# RGB2HDMI.net
KiCad netlist of a schematic drawn in Altium Designer
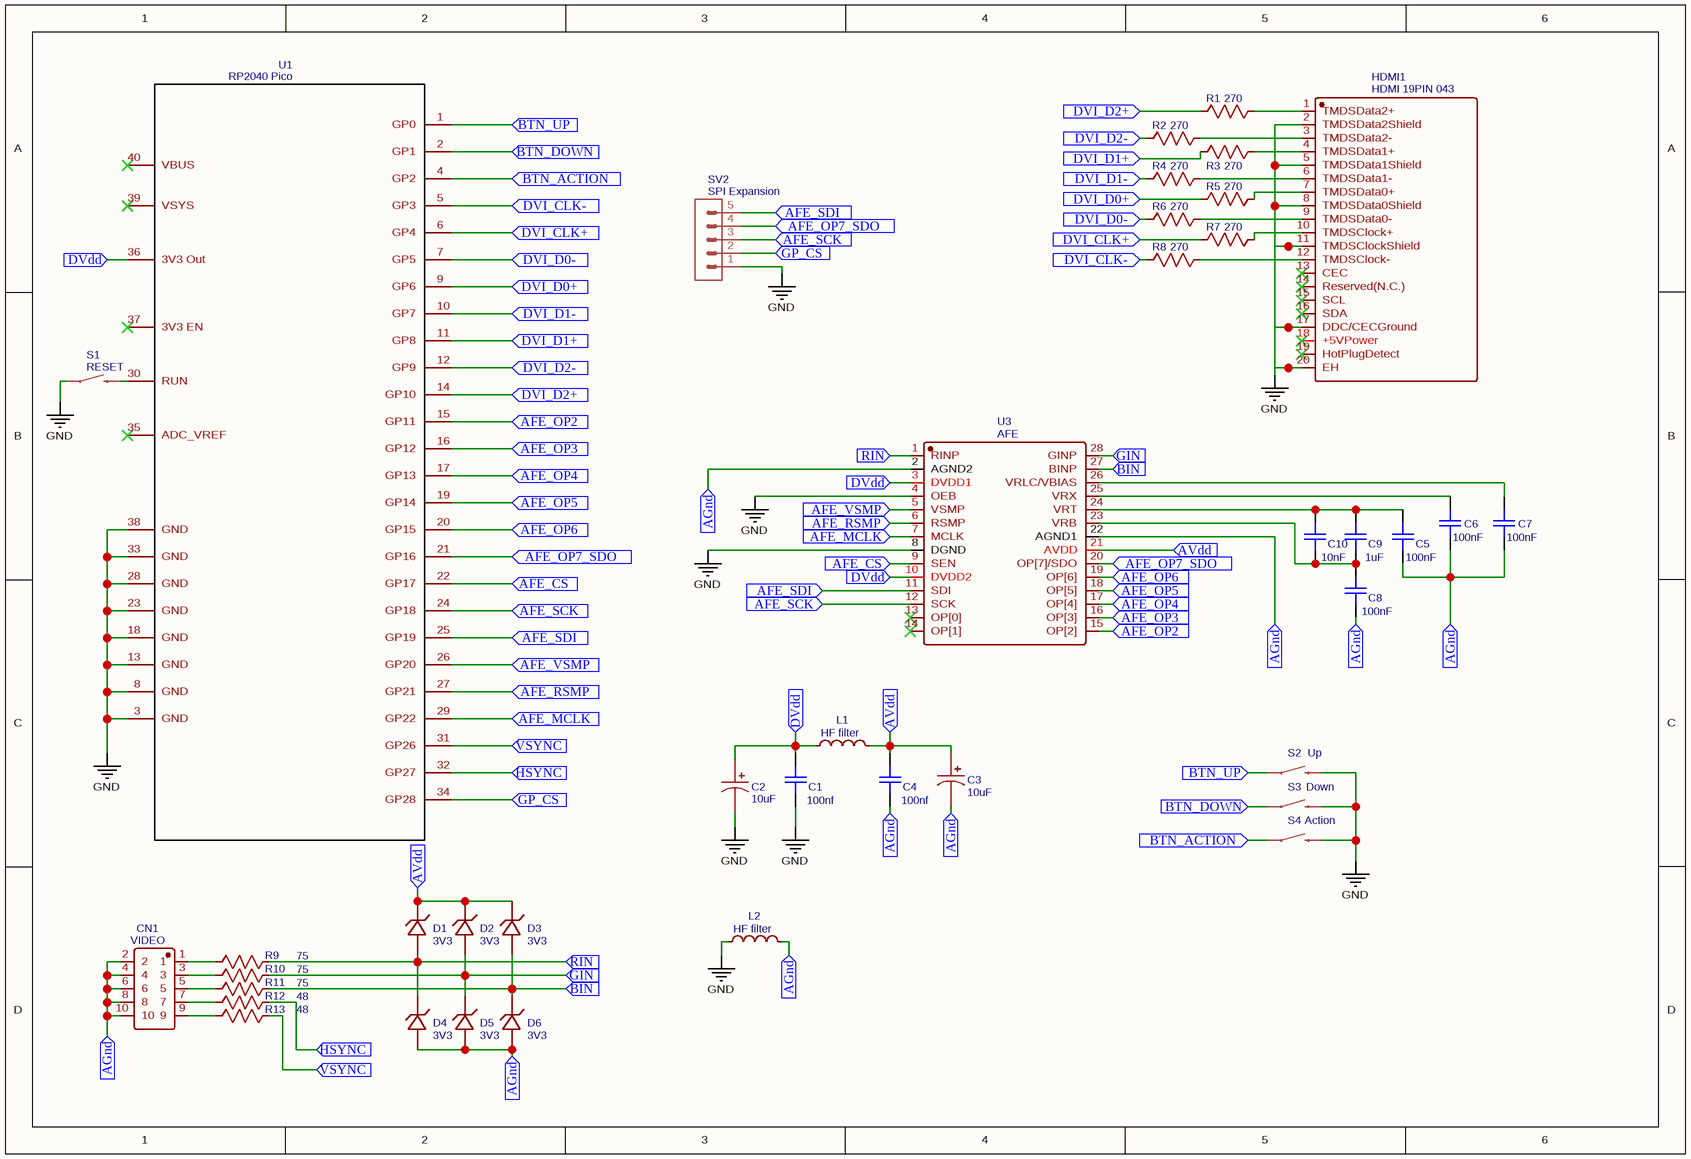
[diagram p0: RGB2HDMI.schdoc]

(export (version "E")
  (design (tool "Eeschema 10.0.6"))
  (components
    (comp (ref "C1")
      (value "100nf")
      (fields
        (field (name "BOM_MANUFACTURER PART") "Ceramic capacitors47PF 3KV")
        (field (name "BOM_SUPPLIER PART") "C19375")
        (field (name "CONTRIBUTOR") "LCSC")
      )
      (libsource (lib "altium-import") (part "root_1_100nf_"))
    )
    (comp (ref "C2")
      (value "10uF")
      (fields
        (field (name "BOM_SUPPLIER PART") "C2162687")
        (field (name "BOM_MANUFACTURER PART") "A700V106M12RATE040")
        (field (name "CONTRIBUTOR") "LCSC")
      )
      (libsource (lib "altium-import") (part "root_3_10uF_"))
    )
    (comp (ref "C3")
      (value "10uF")
      (fields
        (field (name "BOM_SUPPLIER PART") "C2162687")
        (field (name "BOM_MANUFACTURER PART") "A700V106M12RATE040")
        (field (name "CONTRIBUTOR") "LCSC")
      )
      (libsource (lib "altium-import") (part "root_3_10uF_"))
    )
    (comp (ref "C4")
      (value "100nf")
      (fields
        (field (name "BOM_MANUFACTURER PART") "Ceramic capacitors47PF 3KV")
        (field (name "BOM_SUPPLIER PART") "C19375")
        (field (name "CONTRIBUTOR") "LCSC")
      )
      (libsource (lib "altium-import") (part "root_1_100nf_"))
    )
    (comp (ref "C5")
      (value "100nF")
      (fields
        (field (name "BOM_MANUFACTURER PART") "Ceramic capacitors47PF 3KV")
        (field (name "BOM_SUPPLIER PART") "C19375")
        (field (name "CONTRIBUTOR") "LCSC")
      )
      (libsource (lib "altium-import") (part "root_1_100nF_"))
    )
    (comp (ref "C6")
      (value "100nF")
      (fields
        (field (name "BOM_MANUFACTURER PART") "Ceramic capacitors47PF 3KV")
        (field (name "BOM_SUPPLIER PART") "C19375")
        (field (name "CONTRIBUTOR") "LCSC")
      )
      (libsource (lib "altium-import") (part "root_3_100nF_"))
    )
    (comp (ref "C7")
      (value "100nF")
      (fields
        (field (name "BOM_MANUFACTURER PART") "Ceramic capacitors47PF 3KV")
        (field (name "BOM_SUPPLIER PART") "C19375")
        (field (name "CONTRIBUTOR") "LCSC")
      )
      (libsource (lib "altium-import") (part "root_3_100nF_"))
    )
    (comp (ref "C8")
      (value "100nF")
      (fields
        (field (name "BOM_MANUFACTURER PART") "Ceramic capacitors47PF 3KV")
        (field (name "BOM_SUPPLIER PART") "C19375")
        (field (name "CONTRIBUTOR") "LCSC")
      )
      (libsource (lib "altium-import") (part "root_1_100nF_"))
    )
    (comp (ref "C9")
      (value "1uF")
      (fields
        (field (name "BOM_MANUFACTURER PART") "Ceramic capacitors47PF 3KV")
        (field (name "BOM_SUPPLIER PART") "C19375")
        (field (name "CONTRIBUTOR") "LCSC")
      )
      (libsource (lib "altium-import") (part "root_1_1uF_"))
    )
    (comp (ref "C10")
      (value "10nF")
      (fields
        (field (name "BOM_MANUFACTURER PART") "Ceramic capacitors47PF 3KV")
        (field (name "BOM_SUPPLIER PART") "C19375")
        (field (name "CONTRIBUTOR") "LCSC")
      )
      (libsource (lib "altium-import") (part "root_1_10nF_"))
    )
    (comp (ref "CN1")
      (value "VIDEO")
      (fields
        (field (name "BOM_SUPPLIER PART") "C881523")
        (field (name "BOM_MANUFACTURER PART") "CNJM2006WV-2X5P-9T")
        (field (name "CONTRIBUTOR") "LCSC")
      )
      (libsource (lib "altium-import") (part "root_0_VIDEO_"))
    )
    (comp (ref "D1")
      (value "3V3")
      (fields
        (field (name "BOM_MANUFACTURER PART") "BZT52H-B43,115")
        (field (name "BOM_SUPPLIER PART") "C179373")
        (field (name "CONTRIBUTOR") "LCSC")
      )
      (libsource (lib "altium-import") (part "root_3_3V3_"))
    )
    (comp (ref "D2")
      (value "3V3")
      (fields
        (field (name "BOM_MANUFACTURER PART") "BZT52H-B43,115")
        (field (name "BOM_SUPPLIER PART") "C179373")
        (field (name "CONTRIBUTOR") "LCSC")
      )
      (libsource (lib "altium-import") (part "root_3_3V3_"))
    )
    (comp (ref "D3")
      (value "3V3")
      (fields
        (field (name "BOM_MANUFACTURER PART") "BZT52H-B43,115")
        (field (name "BOM_SUPPLIER PART") "C179373")
        (field (name "CONTRIBUTOR") "LCSC")
      )
      (libsource (lib "altium-import") (part "root_3_3V3_"))
    )
    (comp (ref "D4")
      (value "3V3")
      (fields
        (field (name "BOM_MANUFACTURER PART") "BZT52H-B43,115")
        (field (name "BOM_SUPPLIER PART") "C179373")
        (field (name "CONTRIBUTOR") "LCSC")
      )
      (libsource (lib "altium-import") (part "root_3_3V3_"))
    )
    (comp (ref "D5")
      (value "3V3")
      (fields
        (field (name "BOM_MANUFACTURER PART") "BZT52H-B43,115")
        (field (name "BOM_SUPPLIER PART") "C179373")
        (field (name "CONTRIBUTOR") "LCSC")
      )
      (libsource (lib "altium-import") (part "root_3_3V3_"))
    )
    (comp (ref "D6")
      (value "3V3")
      (fields
        (field (name "BOM_MANUFACTURER PART") "BZT52H-B43,115")
        (field (name "BOM_SUPPLIER PART") "C179373")
        (field (name "CONTRIBUTOR") "LCSC")
      )
      (libsource (lib "altium-import") (part "root_3_3V3_"))
    )
    (comp (ref "HDMI1")
      (value "HDMI 19PIN 043")
      (fields (field (name "BOM_SUPPLIER PART") "C2858275") (field (name "CONTRIBUTOR") "LCSC"))
      (libsource (lib "altium-import") (part "root_0_HDMI 19PIN 043_"))
    )
    (comp (ref "L1")
      (value "HF filter")
      (fields
        (field (name "BOM_SUPPLIER PART") "C2661928")
        (field (name "BOM_MANUFACTURER PART") "ACML-0603H-601-T")
        (field (name "CONTRIBUTOR") "LCSC")
      )
      (libsource (lib "altium-import") (part "root_0_HF filter_"))
    )
    (comp (ref "L2")
      (value "HF filter")
      (fields
        (field (name "BOM_SUPPLIER PART") "C2661928")
        (field (name "BOM_MANUFACTURER PART") "ACML-0603H-601-T")
        (field (name "CONTRIBUTOR") "LCSC")
      )
      (libsource (lib "altium-import") (part "root_0_HF filter_"))
    )
    (comp (ref "R1")
      (value "270")
      (fields (field (name "CONTRIBUTOR") "LCEDA_Lib"))
      (libsource (lib "altium-import") (part "root_0_270_"))
    )
    (comp (ref "R2")
      (value "270")
      (fields (field (name "CONTRIBUTOR") "LCEDA_Lib"))
      (libsource (lib "altium-import") (part "root_0_270_"))
    )
    (comp (ref "R3")
      (value "270")
      (fields (field (name "CONTRIBUTOR") "LCEDA_Lib"))
      (libsource (lib "altium-import") (part "root_0_270_"))
    )
    (comp (ref "R4")
      (value "270")
      (fields (field (name "CONTRIBUTOR") "LCEDA_Lib"))
      (libsource (lib "altium-import") (part "root_0_270_"))
    )
    (comp (ref "R5")
      (value "270")
      (fields (field (name "CONTRIBUTOR") "LCEDA_Lib"))
      (libsource (lib "altium-import") (part "root_0_270_"))
    )
    (comp (ref "R6")
      (value "270")
      (fields (field (name "CONTRIBUTOR") "LCEDA_Lib"))
      (libsource (lib "altium-import") (part "root_0_270_"))
    )
    (comp (ref "R7")
      (value "270")
      (fields (field (name "CONTRIBUTOR") "LCEDA_Lib"))
      (libsource (lib "altium-import") (part "root_0_270_"))
    )
    (comp (ref "R8")
      (value "270")
      (fields (field (name "CONTRIBUTOR") "LCEDA_Lib"))
      (libsource (lib "altium-import") (part "root_0_270_"))
    )
    (comp (ref "R9")
      (value "75")
      (fields (field (name "CONTRIBUTOR") "LCEDA_Lib"))
      (libsource (lib "altium-import") (part "root_0_75_"))
    )
    (comp (ref "R10")
      (value "75")
      (fields (field (name "CONTRIBUTOR") "LCEDA_Lib"))
      (libsource (lib "altium-import") (part "root_0_75_"))
    )
    (comp (ref "R11")
      (value "75")
      (fields (field (name "CONTRIBUTOR") "LCEDA_Lib"))
      (libsource (lib "altium-import") (part "root_0_75_"))
    )
    (comp (ref "R12")
      (value "48")
      (fields (field (name "CONTRIBUTOR") "LCEDA_Lib"))
      (libsource (lib "altium-import") (part "root_0_48_"))
    )
    (comp (ref "R13")
      (value "48")
      (fields (field (name "CONTRIBUTOR") "LCEDA_Lib"))
      (libsource (lib "altium-import") (part "root_0_48_"))
    )
    (comp (ref "S1")
      (value "RESET")
      (fields (field (name "CONTRIBUTOR") "Owen Pratama"))
      (libsource (lib "altium-import") (part "root_0_RESET_"))
    )
    (comp (ref "S2")
      (value "Up")
      (fields (field (name "CONTRIBUTOR") "Owen Pratama"))
      (libsource (lib "altium-import") (part "root_0_Up_"))
    )
    (comp (ref "S3")
      (value "Down")
      (fields (field (name "CONTRIBUTOR") "Owen Pratama"))
      (libsource (lib "altium-import") (part "root_0_Down_"))
    )
    (comp (ref "S4")
      (value "Action")
      (fields (field (name "CONTRIBUTOR") "Owen Pratama"))
      (libsource (lib "altium-import") (part "root_0_Action_"))
    )
    (comp (ref "SV2")
      (value "SPI Expansion")
      (fields (field (name "CONTRIBUTOR") "Mr Tesla"))
      (libsource (lib "altium-import") (part "root_0_SPI Expansion_"))
    )
    (comp (ref "U1")
      (value "RP2040 Pico")
      (fields (field (name "CONTRIBUTOR") "gordond1980"))
      (libsource (lib "altium-import") (part "root_0_RP2040 Pico_"))
    )
    (comp (ref "U3")
      (value "AFE")
      (fields
        (field (name "BOM_SUPPLIER PART") "C431490")
        (field (name "BOM_MANUFACTURER PART") "WM8213SCDS/V")
        (field (name "CONTRIBUTOR") "LCSC")
      )
      (libsource (lib "altium-import") (part "root_0_AFE_"))
    )
  )
  (nets
    (net (code "1") (name "/AFE_CS") (class "Default")
      (node (ref "U1") (pin "22") (pinfunction "GP17_22") (pintype "passive"))
      (node (ref "U3") (pin "9") (pinfunction "SEN_9") (pintype "passive"))
    )
    (net (code "2") (name "/AFE_MCLK") (class "Default")
      (node (ref "U1") (pin "29") (pinfunction "GP22_29") (pintype "passive"))
      (node (ref "U3") (pin "7") (pinfunction "MCLK_7") (pintype "passive"))
    )
    (net (code "3") (name "/AFE_OP2") (class "Default")
      (node (ref "U1") (pin "15") (pinfunction "GP11_15") (pintype "passive"))
      (node (ref "U3") (pin "15") (pinfunction "OP[2]_15") (pintype "passive"))
    )
    (net (code "4") (name "/AFE_OP3") (class "Default")
      (node (ref "U1") (pin "16") (pinfunction "GP12_16") (pintype "passive"))
      (node (ref "U3") (pin "16") (pinfunction "OP[3]_16") (pintype "passive"))
    )
    (net (code "5") (name "/AFE_OP4") (class "Default")
      (node (ref "U1") (pin "17") (pinfunction "GP13_17") (pintype "passive"))
      (node (ref "U3") (pin "17") (pinfunction "OP[4]_17") (pintype "passive"))
    )
    (net (code "6") (name "/AFE_OP5") (class "Default")
      (node (ref "U1") (pin "19") (pinfunction "GP14_19") (pintype "passive"))
      (node (ref "U3") (pin "18") (pinfunction "OP[5]_18") (pintype "passive"))
    )
    (net (code "7") (name "/AFE_OP6") (class "Default")
      (node (ref "U1") (pin "20") (pinfunction "GP15_20") (pintype "passive"))
      (node (ref "U3") (pin "19") (pinfunction "OP[6]_19") (pintype "passive"))
    )
    (net (code "8") (name "/AFE_OP7_SDO") (class "Default")
      (node (ref "SV2") (pin "4") (pinfunction "4_4") (pintype "passive"))
      (node (ref "U1") (pin "21") (pinfunction "GP16_21") (pintype "passive"))
      (node (ref "U3") (pin "20") (pinfunction "OP[7]/SDO_20") (pintype "passive"))
    )
    (net (code "9") (name "/AFE_RSMP") (class "Default")
      (node (ref "U1") (pin "27") (pinfunction "GP21_27") (pintype "passive"))
      (node (ref "U3") (pin "6") (pinfunction "RSMP_6") (pintype "passive"))
    )
    (net (code "10") (name "/AFE_SCK") (class "Default")
      (node (ref "SV2") (pin "3") (pinfunction "3_3") (pintype "passive"))
      (node (ref "U1") (pin "24") (pinfunction "GP18_24") (pintype "passive"))
      (node (ref "U3") (pin "12") (pinfunction "SCK_12") (pintype "passive"))
    )
    (net (code "11") (name "/AFE_SDI") (class "Default")
      (node (ref "SV2") (pin "5") (pinfunction "5_5") (pintype "passive"))
      (node (ref "U1") (pin "25") (pinfunction "GP19_25") (pintype "passive"))
      (node (ref "U3") (pin "11") (pinfunction "SDI_11") (pintype "passive"))
    )
    (net (code "12") (name "/AFE_VSMP") (class "Default")
      (node (ref "U1") (pin "26") (pinfunction "GP20_26") (pintype "passive"))
      (node (ref "U3") (pin "5") (pinfunction "VSMP_5") (pintype "passive"))
    )
    (net (code "13") (name "/AGnd") (class "Default")
      (node (ref "C3") (pin "2") (pinfunction "2_2") (pintype "passive"))
      (node (ref "C4") (pin "1") (pinfunction "1_1") (pintype "passive"))
      (node (ref "C5") (pin "1") (pinfunction "1_1") (pintype "passive"))
      (node (ref "C6") (pin "2") (pinfunction "2_2") (pintype "passive"))
      (node (ref "C7") (pin "2") (pinfunction "2_2") (pintype "passive"))
      (node (ref "C8") (pin "1") (pinfunction "1_1") (pintype "passive"))
      (node (ref "CN1") (pin "10") (pinfunction "10_10") (pintype "passive"))
      (node (ref "CN1") (pin "2") (pinfunction "2_2") (pintype "passive"))
      (node (ref "CN1") (pin "4") (pinfunction "4_4") (pintype "passive"))
      (node (ref "CN1") (pin "6") (pinfunction "6_6") (pintype "passive"))
      (node (ref "CN1") (pin "8") (pinfunction "8_8") (pintype "passive"))
      (node (ref "D4") (pin "2") (pinfunction "A_2") (pintype "passive"))
      (node (ref "D5") (pin "2") (pinfunction "A_2") (pintype "passive"))
      (node (ref "D6") (pin "2") (pinfunction "A_2") (pintype "passive"))
      (node (ref "L2") (pin "2") (pinfunction "2_2") (pintype "passive"))
      (node (ref "U3") (pin "2") (pinfunction "AGND2_2") (pintype "passive"))
      (node (ref "U3") (pin "22") (pinfunction "AGND1_22") (pintype "passive"))
    )
    (net (code "14") (name "/AVdd") (class "Default")
      (node (ref "C3") (pin "1") (pinfunction "1_1") (pintype "passive"))
      (node (ref "C4") (pin "2") (pinfunction "2_2") (pintype "passive"))
      (node (ref "D1") (pin "1") (pinfunction "K_1") (pintype "passive"))
      (node (ref "D2") (pin "1") (pinfunction "K_1") (pintype "passive"))
      (node (ref "D3") (pin "1") (pinfunction "K_1") (pintype "passive"))
      (node (ref "L1") (pin "2") (pinfunction "2_2") (pintype "passive"))
      (node (ref "U3") (pin "21") (pinfunction "AVDD_21") (pintype "passive"))
    )
    (net (code "15") (name "/BIN") (class "Default")
      (node (ref "D3") (pin "2") (pinfunction "A_2") (pintype "passive"))
      (node (ref "D6") (pin "1") (pinfunction "K_1") (pintype "passive"))
      (node (ref "R11") (pin "2") (pinfunction "2_2") (pintype "passive"))
      (node (ref "U3") (pin "27") (pinfunction "BINP_27") (pintype "passive"))
    )
    (net (code "16") (name "/BTN_ACTION") (class "Default")
      (node (ref "S4") (pin "1") (pinfunction "1_1") (pintype "passive"))
      (node (ref "U1") (pin "4") (pinfunction "GP2_4") (pintype "passive"))
    )
    (net (code "17") (name "/BTN_DOWN") (class "Default")
      (node (ref "S3") (pin "1") (pinfunction "1_1") (pintype "passive"))
      (node (ref "U1") (pin "2") (pinfunction "GP1_2") (pintype "passive"))
    )
    (net (code "18") (name "/BTN_UP") (class "Default")
      (node (ref "S2") (pin "1") (pinfunction "1_1") (pintype "passive"))
      (node (ref "U1") (pin "1") (pinfunction "GP0_1") (pintype "passive"))
    )
    (net (code "19") (name "/DVI_CLK+") (class "Default")
      (node (ref "R7") (pin "1") (pinfunction "1_1") (pintype "passive"))
      (node (ref "U1") (pin "6") (pinfunction "GP4_6") (pintype "passive"))
    )
    (net (code "20") (name "/DVI_CLK-") (class "Default")
      (node (ref "R8") (pin "1") (pinfunction "1_1") (pintype "passive"))
      (node (ref "U1") (pin "5") (pinfunction "GP3_5") (pintype "passive"))
    )
    (net (code "21") (name "/DVI_D0+") (class "Default")
      (node (ref "R5") (pin "1") (pinfunction "1_1") (pintype "passive"))
      (node (ref "U1") (pin "9") (pinfunction "GP6_9") (pintype "passive"))
    )
    (net (code "22") (name "/DVI_D0-") (class "Default")
      (node (ref "R6") (pin "1") (pinfunction "1_1") (pintype "passive"))
      (node (ref "U1") (pin "7") (pinfunction "GP5_7") (pintype "passive"))
    )
    (net (code "23") (name "/DVI_D1+") (class "Default")
      (node (ref "R3") (pin "1") (pinfunction "1_1") (pintype "passive"))
      (node (ref "U1") (pin "11") (pinfunction "GP8_11") (pintype "passive"))
    )
    (net (code "24") (name "/DVI_D1-") (class "Default")
      (node (ref "R4") (pin "1") (pinfunction "1_1") (pintype "passive"))
      (node (ref "U1") (pin "10") (pinfunction "GP7_10") (pintype "passive"))
    )
    (net (code "25") (name "/DVI_D2+") (class "Default")
      (node (ref "R1") (pin "1") (pinfunction "1_1") (pintype "passive"))
      (node (ref "U1") (pin "14") (pinfunction "GP10_14") (pintype "passive"))
    )
    (net (code "26") (name "/DVI_D2-") (class "Default")
      (node (ref "R2") (pin "1") (pinfunction "1_1") (pintype "passive"))
      (node (ref "U1") (pin "12") (pinfunction "GP9_12") (pintype "passive"))
    )
    (net (code "27") (name "/DVdd") (class "Default")
      (node (ref "C1") (pin "2") (pinfunction "2_2") (pintype "passive"))
      (node (ref "C2") (pin "1") (pinfunction "1_1") (pintype "passive"))
      (node (ref "L1") (pin "1") (pinfunction "1_1") (pintype "passive"))
      (node (ref "U1") (pin "36") (pinfunction "3V3_Out_36") (pintype "passive"))
      (node (ref "U3") (pin "10") (pinfunction "DVDD2_10") (pintype "passive"))
      (node (ref "U3") (pin "3") (pinfunction "DVDD1_3") (pintype "passive"))
    )
    (net (code "28") (name "/GIN") (class "Default")
      (node (ref "D2") (pin "2") (pinfunction "A_2") (pintype "passive"))
      (node (ref "D5") (pin "1") (pinfunction "K_1") (pintype "passive"))
      (node (ref "R10") (pin "2") (pinfunction "2_2") (pintype "passive"))
      (node (ref "U3") (pin "28") (pinfunction "GINP_28") (pintype "passive"))
    )
    (net (code "29") (name "/GP_CS") (class "Default")
      (node (ref "SV2") (pin "2") (pinfunction "2_2") (pintype "passive"))
      (node (ref "U1") (pin "34") (pinfunction "GP28_34") (pintype "passive"))
    )
    (net (code "30") (name "/HSYNC") (class "Default")
      (node (ref "R12") (pin "2") (pinfunction "2_2") (pintype "passive"))
      (node (ref "U1") (pin "32") (pinfunction "GP27_32") (pintype "passive"))
    )
    (net (code "31") (name "/RIN") (class "Default")
      (node (ref "D1") (pin "2") (pinfunction "A_2") (pintype "passive"))
      (node (ref "D4") (pin "1") (pinfunction "K_1") (pintype "passive"))
      (node (ref "R9") (pin "2") (pinfunction "2_2") (pintype "passive"))
      (node (ref "U3") (pin "1") (pinfunction "RINP_1") (pintype "passive"))
    )
    (net (code "32") (name "/VSYNC") (class "Default")
      (node (ref "R13") (pin "2") (pinfunction "2_2") (pintype "passive"))
      (node (ref "U1") (pin "31") (pinfunction "GP26_31") (pintype "passive"))
    )
    (net (code "33") (name "GND") (class "Default")
      (node (ref "C1") (pin "1") (pinfunction "1_1") (pintype "passive"))
      (node (ref "C2") (pin "2") (pinfunction "2_2") (pintype "passive"))
      (node (ref "HDMI1") (pin "11") (pinfunction "TMDSClockShield_11") (pintype "passive"))
      (node (ref "HDMI1") (pin "17") (pinfunction "DDC/CECGround_17") (pintype "passive"))
      (node (ref "HDMI1") (pin "2") (pinfunction "TMDSData2Shield_2") (pintype "passive"))
      (node (ref "HDMI1") (pin "20") (pinfunction "EH_20") (pintype "passive"))
      (node (ref "HDMI1") (pin "5") (pinfunction "TMDSData1Shield_5") (pintype "passive"))
      (node (ref "HDMI1") (pin "8") (pinfunction "TMDSData0Shield_8") (pintype "passive"))
      (node (ref "L2") (pin "1") (pinfunction "1_1") (pintype "passive"))
      (node (ref "S1") (pin "1") (pinfunction "1_1") (pintype "passive"))
      (node (ref "S2") (pin "3") (pinfunction "2_3") (pintype "passive"))
      (node (ref "S3") (pin "3") (pinfunction "2_3") (pintype "passive"))
      (node (ref "S4") (pin "3") (pinfunction "2_3") (pintype "passive"))
      (node (ref "SV2") (pin "1") (pinfunction "1_1") (pintype "passive"))
      (node (ref "U1") (pin "13") (pinfunction "GND_13") (pintype "passive"))
      (node (ref "U1") (pin "18") (pinfunction "GND_18") (pintype "passive"))
      (node (ref "U1") (pin "23") (pinfunction "GND_23") (pintype "passive"))
      (node (ref "U1") (pin "28") (pinfunction "GND_28") (pintype "passive"))
      (node (ref "U1") (pin "3") (pinfunction "GND_3") (pintype "passive"))
      (node (ref "U1") (pin "33") (pinfunction "GND_33") (pintype "passive"))
      (node (ref "U1") (pin "38") (pinfunction "GND_38") (pintype "passive"))
      (node (ref "U1") (pin "8") (pinfunction "GND_8") (pintype "passive"))
      (node (ref "U3") (pin "4") (pinfunction "OEB_4") (pintype "passive"))
      (node (ref "U3") (pin "8") (pinfunction "DGND_8") (pintype "passive"))
    )
    (net (code "34") (name "Net-(CN1-Pad1)") (class "Default")
      (node (ref "CN1") (pin "1") (pinfunction "1_1") (pintype "passive"))
      (node (ref "R9") (pin "1") (pinfunction "1_1") (pintype "passive"))
    )
    (net (code "35") (name "Net-(CN1-Pad3)") (class "Default")
      (node (ref "CN1") (pin "3") (pinfunction "3_3") (pintype "passive"))
      (node (ref "R10") (pin "1") (pinfunction "1_1") (pintype "passive"))
    )
    (net (code "36") (name "Net-(CN1-Pad5)") (class "Default")
      (node (ref "CN1") (pin "5") (pinfunction "5_5") (pintype "passive"))
      (node (ref "R11") (pin "1") (pinfunction "1_1") (pintype "passive"))
    )
    (net (code "37") (name "Net-(CN1-Pad7)") (class "Default")
      (node (ref "CN1") (pin "7") (pinfunction "7_7") (pintype "passive"))
      (node (ref "R12") (pin "1") (pinfunction "1_1") (pintype "passive"))
    )
    (net (code "38") (name "Net-(CN1-Pad9)") (class "Default")
      (node (ref "CN1") (pin "9") (pinfunction "9_9") (pintype "passive"))
      (node (ref "R13") (pin "1") (pinfunction "1_1") (pintype "passive"))
    )
    (net (code "39") (name "Net-(HDMI1-TMDSClock+)") (class "Default")
      (node (ref "HDMI1") (pin "10") (pinfunction "TMDSClock+_10") (pintype "passive"))
      (node (ref "R7") (pin "2") (pinfunction "2_2") (pintype "passive"))
    )
    (net (code "40") (name "Net-(HDMI1-TMDSClock-)") (class "Default")
      (node (ref "HDMI1") (pin "12") (pinfunction "TMDSClock-_12") (pintype "passive"))
      (node (ref "R8") (pin "2") (pinfunction "2_2") (pintype "passive"))
    )
    (net (code "41") (name "Net-(HDMI1-TMDSData0+)") (class "Default")
      (node (ref "HDMI1") (pin "7") (pinfunction "TMDSData0+_7") (pintype "passive"))
      (node (ref "R5") (pin "2") (pinfunction "2_2") (pintype "passive"))
    )
    (net (code "42") (name "Net-(HDMI1-TMDSData0-)") (class "Default")
      (node (ref "HDMI1") (pin "9") (pinfunction "TMDSData0-_9") (pintype "passive"))
      (node (ref "R6") (pin "2") (pinfunction "2_2") (pintype "passive"))
    )
    (net (code "43") (name "Net-(HDMI1-TMDSData1+)") (class "Default")
      (node (ref "HDMI1") (pin "4") (pinfunction "TMDSData1+_4") (pintype "passive"))
      (node (ref "R3") (pin "2") (pinfunction "2_2") (pintype "passive"))
    )
    (net (code "44") (name "Net-(HDMI1-TMDSData1-)") (class "Default")
      (node (ref "HDMI1") (pin "6") (pinfunction "TMDSData1-_6") (pintype "passive"))
      (node (ref "R4") (pin "2") (pinfunction "2_2") (pintype "passive"))
    )
    (net (code "45") (name "Net-(HDMI1-TMDSData2+)") (class "Default")
      (node (ref "HDMI1") (pin "1") (pinfunction "TMDSData2+_1") (pintype "passive"))
      (node (ref "R1") (pin "2") (pinfunction "2_2") (pintype "passive"))
    )
    (net (code "46") (name "Net-(HDMI1-TMDSData2-)") (class "Default")
      (node (ref "HDMI1") (pin "3") (pinfunction "TMDSData2-_3") (pintype "passive"))
      (node (ref "R2") (pin "2") (pinfunction "2_2") (pintype "passive"))
    )
    (net (code "47") (name "Net-(S1-2)") (class "Default")
      (node (ref "S1") (pin "3") (pinfunction "2_3") (pintype "passive"))
      (node (ref "U1") (pin "30") (pinfunction "RUN_30") (pintype "passive"))
    )
    (net (code "48") (name "Net-(U3-VRB)") (class "Default")
      (node (ref "C10") (pin "1") (pinfunction "1_1") (pintype "passive"))
      (node (ref "C8") (pin "2") (pinfunction "2_2") (pintype "passive"))
      (node (ref "C9") (pin "1") (pinfunction "1_1") (pintype "passive"))
      (node (ref "U3") (pin "23") (pinfunction "VRB_23") (pintype "passive"))
    )
    (net (code "49") (name "Net-(U3-VRLC{slash}VBIAS)") (class "Default")
      (node (ref "C7") (pin "1") (pinfunction "1_1") (pintype "passive"))
      (node (ref "U3") (pin "26") (pinfunction "VRLC/VBIAS_26") (pintype "passive"))
    )
    (net (code "50") (name "Net-(U3-VRT)") (class "Default")
      (node (ref "C10") (pin "2") (pinfunction "2_2") (pintype "passive"))
      (node (ref "C5") (pin "2") (pinfunction "2_2") (pintype "passive"))
      (node (ref "C9") (pin "2") (pinfunction "2_2") (pintype "passive"))
      (node (ref "U3") (pin "24") (pinfunction "VRT_24") (pintype "passive"))
    )
    (net (code "51") (name "Net-(U3-VRX)") (class "Default")
      (node (ref "C6") (pin "1") (pinfunction "1_1") (pintype "passive"))
      (node (ref "U3") (pin "25") (pinfunction "VRX_25") (pintype "passive"))
    )
    (net (code "52") (name "unconnected-(HDMI1-+5VPower-Pad18)") (class "Default")
      (node (ref "HDMI1") (pin "18") (pinfunction "+5VPower_18") (pintype "passive+no_connect"))
    )
    (net (code "53") (name "unconnected-(HDMI1-CEC-Pad13)") (class "Default")
      (node (ref "HDMI1") (pin "13") (pinfunction "CEC_13") (pintype "passive+no_connect"))
    )
    (net (code "54") (name "unconnected-(HDMI1-HotPlugDetect-Pad19)") (class "Default")
      (node (ref "HDMI1") (pin "19") (pinfunction "HotPlugDetect_19") (pintype "passive+no_connect"))
    )
    (net (code "55") (name "unconnected-(HDMI1-Reserved(N.C.)-Pad14)") (class "Default")
      (node (ref "HDMI1") (pin "14") (pinfunction "Reserved(N.C.)_14") (pintype "passive+no_connect"))
    )
    (net (code "56") (name "unconnected-(HDMI1-SCL-Pad15)") (class "Default")
      (node (ref "HDMI1") (pin "15") (pinfunction "SCL_15") (pintype "passive+no_connect"))
    )
    (net (code "57") (name "unconnected-(HDMI1-SDA-Pad16)") (class "Default")
      (node (ref "HDMI1") (pin "16") (pinfunction "SDA_16") (pintype "passive+no_connect"))
    )
    (net (code "58") (name "unconnected-(U1-3V3_EN-Pad37)") (class "Default")
      (node (ref "U1") (pin "37") (pinfunction "3V3_EN_37") (pintype "passive+no_connect"))
    )
    (net (code "59") (name "unconnected-(U1-ADC_VREF-Pad35)") (class "Default")
      (node (ref "U1") (pin "35") (pinfunction "ADC_VREF_35") (pintype "passive+no_connect"))
    )
    (net (code "60") (name "unconnected-(U1-VBUS-Pad40)") (class "Default")
      (node (ref "U1") (pin "40") (pinfunction "VBUS_40") (pintype "passive+no_connect"))
    )
    (net (code "61") (name "unconnected-(U1-VSYS-Pad39)") (class "Default")
      (node (ref "U1") (pin "39") (pinfunction "VSYS_39") (pintype "passive+no_connect"))
    )
    (net (code "62") (name "unconnected-(U3-OP[0]-Pad13)") (class "Default")
      (node (ref "U3") (pin "13") (pinfunction "OP[0]_13") (pintype "passive+no_connect"))
    )
    (net (code "63") (name "unconnected-(U3-OP[1]-Pad14)") (class "Default")
      (node (ref "U3") (pin "14") (pinfunction "OP[1]_14") (pintype "passive+no_connect"))
    )
  )
)
